# Encodeurs_Schematic.net
KiCad netlist of a schematic drawn in Altium Designer
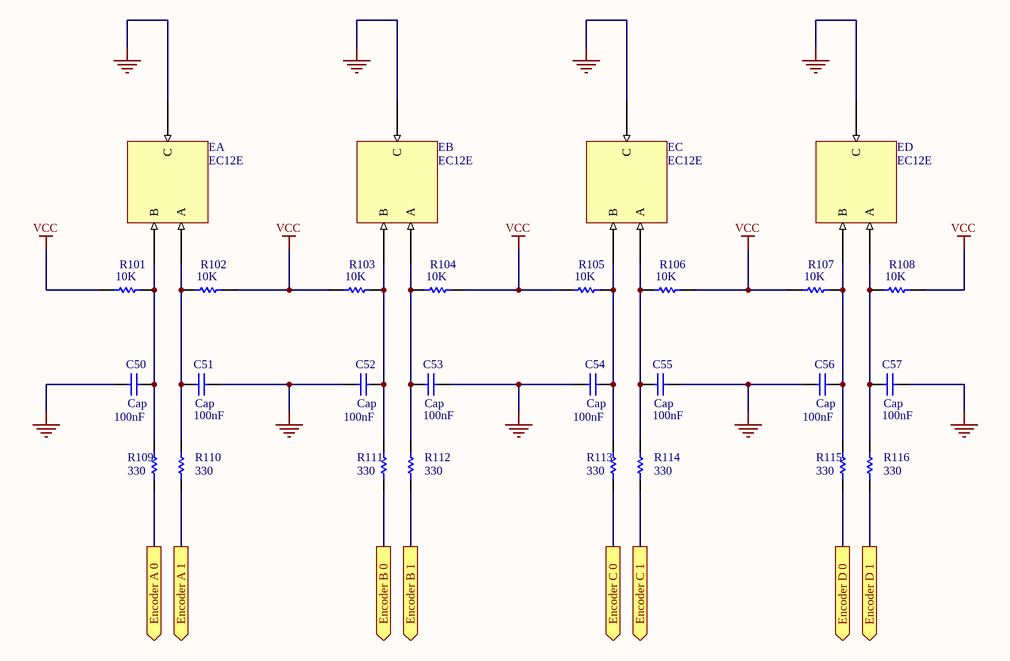
[diagram p0: Encodeurs.Schematic.SchDoc]

(export (version "E")
  (design (tool "Eeschema 10.0.6"))
  (components
    (comp (ref "C50")
      (value "Cap")
      (footprint "CAPC1608N")
      (description "Capacitor")
      (fields (field (name "ALTIUM_VALUE") "100nF") (field (name "PUBLISHER") "Altium Limited"))
      (libsource (lib "Miscellaneous Devices") (part "Cap"))
    )
    (comp (ref "C51")
      (value "Cap")
      (footprint "CAPC1608N")
      (description "Capacitor")
      (fields (field (name "ALTIUM_VALUE") "100nF") (field (name "PUBLISHER") "Altium Limited"))
      (libsource (lib "Miscellaneous Devices") (part "Cap"))
    )
    (comp (ref "C52")
      (value "Cap")
      (footprint "CAPC1608N")
      (description "Capacitor")
      (fields (field (name "ALTIUM_VALUE") "100nF") (field (name "PUBLISHER") "Altium Limited"))
      (libsource (lib "Miscellaneous Devices") (part "Cap"))
    )
    (comp (ref "C53")
      (value "Cap")
      (footprint "CAPC1608N")
      (description "Capacitor")
      (fields (field (name "ALTIUM_VALUE") "100nF") (field (name "PUBLISHER") "Altium Limited"))
      (libsource (lib "Miscellaneous Devices") (part "Cap"))
    )
    (comp (ref "C54")
      (value "Cap")
      (footprint "CAPC1608N")
      (description "Capacitor")
      (fields (field (name "ALTIUM_VALUE") "100nF") (field (name "PUBLISHER") "Altium Limited"))
      (libsource (lib "Miscellaneous Devices") (part "Cap"))
    )
    (comp (ref "C55")
      (value "Cap")
      (footprint "CAPC1608N")
      (description "Capacitor")
      (fields (field (name "ALTIUM_VALUE") "100nF") (field (name "PUBLISHER") "Altium Limited"))
      (libsource (lib "Miscellaneous Devices") (part "Cap"))
    )
    (comp (ref "C56")
      (value "Cap")
      (footprint "CAPC1608N")
      (description "Capacitor")
      (fields (field (name "ALTIUM_VALUE") "100nF") (field (name "PUBLISHER") "Altium Limited"))
      (libsource (lib "Miscellaneous Devices") (part "Cap"))
    )
    (comp (ref "C57")
      (value "Cap")
      (footprint "CAPC1608N")
      (description "Capacitor")
      (fields (field (name "ALTIUM_VALUE") "100nF") (field (name "PUBLISHER") "Altium Limited"))
      (libsource (lib "Miscellaneous Devices") (part "Cap"))
    )
    (comp (ref "EA")
      (value "EC12E")
      (footprint "EC12E")
      (libsource (lib "SynthyTwo.Components") (part "EC12E"))
    )
    (comp (ref "EB")
      (value "EC12E")
      (footprint "EC12E")
      (libsource (lib "SynthyTwo.Components") (part "EC12E"))
    )
    (comp (ref "EC")
      (value "EC12E")
      (footprint "EC12E")
      (libsource (lib "SynthyTwo.Components") (part "EC12E"))
    )
    (comp (ref "ED")
      (value "EC12E")
      (footprint "EC12E")
      (libsource (lib "SynthyTwo.Components") (part "EC12E"))
    )
    (comp (ref "R101")
      (value "10K")
      (footprint "CAPC1608N")
      (description "Resistor")
      (fields (field (name "PUBLISHER") "Altium Limited"))
      (libsource (lib "Miscellaneous Devices") (part "Res1"))
    )
    (comp (ref "R102")
      (value "10K")
      (footprint "CAPC1608N")
      (description "Resistor")
      (fields (field (name "PUBLISHER") "Altium Limited"))
      (libsource (lib "Miscellaneous Devices") (part "Res1"))
    )
    (comp (ref "R103")
      (value "10K")
      (footprint "CAPC1608N")
      (description "Resistor")
      (fields (field (name "PUBLISHER") "Altium Limited"))
      (libsource (lib "Miscellaneous Devices") (part "Res1"))
    )
    (comp (ref "R104")
      (value "10K")
      (footprint "CAPC1608N")
      (description "Resistor")
      (fields (field (name "PUBLISHER") "Altium Limited"))
      (libsource (lib "Miscellaneous Devices") (part "Res1"))
    )
    (comp (ref "R105")
      (value "10K")
      (footprint "CAPC1608N")
      (description "Resistor")
      (fields (field (name "PUBLISHER") "Altium Limited"))
      (libsource (lib "Miscellaneous Devices") (part "Res1"))
    )
    (comp (ref "R106")
      (value "10K")
      (footprint "CAPC1608N")
      (description "Resistor")
      (fields (field (name "PUBLISHER") "Altium Limited"))
      (libsource (lib "Miscellaneous Devices") (part "Res1"))
    )
    (comp (ref "R107")
      (value "10K")
      (footprint "CAPC1608N")
      (description "Resistor")
      (fields (field (name "PUBLISHER") "Altium Limited"))
      (libsource (lib "Miscellaneous Devices") (part "Res1"))
    )
    (comp (ref "R108")
      (value "10K")
      (footprint "CAPC1608N")
      (description "Resistor")
      (fields (field (name "PUBLISHER") "Altium Limited"))
      (libsource (lib "Miscellaneous Devices") (part "Res1"))
    )
    (comp (ref "R109")
      (value "330")
      (footprint "CAPC1608N")
      (description "Resistor")
      (fields (field (name "PUBLISHER") "Altium Limited"))
      (libsource (lib "Miscellaneous Devices") (part "Res1"))
    )
    (comp (ref "R110")
      (value "330")
      (footprint "CAPC1608N")
      (description "Resistor")
      (fields (field (name "PUBLISHER") "Altium Limited"))
      (libsource (lib "Miscellaneous Devices") (part "Res1"))
    )
    (comp (ref "R111")
      (value "330")
      (footprint "CAPC1608N")
      (description "Resistor")
      (fields (field (name "PUBLISHER") "Altium Limited"))
      (libsource (lib "Miscellaneous Devices") (part "Res1"))
    )
    (comp (ref "R112")
      (value "330")
      (footprint "CAPC1608N")
      (description "Resistor")
      (fields (field (name "PUBLISHER") "Altium Limited"))
      (libsource (lib "Miscellaneous Devices") (part "Res1"))
    )
    (comp (ref "R113")
      (value "330")
      (footprint "CAPC1608N")
      (description "Resistor")
      (fields (field (name "PUBLISHER") "Altium Limited"))
      (libsource (lib "Miscellaneous Devices") (part "Res1"))
    )
    (comp (ref "R114")
      (value "330")
      (footprint "CAPC1608N")
      (description "Resistor")
      (fields (field (name "PUBLISHER") "Altium Limited"))
      (libsource (lib "Miscellaneous Devices") (part "Res1"))
    )
    (comp (ref "R115")
      (value "330")
      (footprint "CAPC1608N")
      (description "Resistor")
      (fields (field (name "PUBLISHER") "Altium Limited"))
      (libsource (lib "Miscellaneous Devices") (part "Res1"))
    )
    (comp (ref "R116")
      (value "330")
      (footprint "CAPC1608N")
      (description "Resistor")
      (fields (field (name "PUBLISHER") "Altium Limited"))
      (libsource (lib "Miscellaneous Devices") (part "Res1"))
    )
  )
  (nets
    (net (code "1") (name "/Encoder A 0") (class "Default")
      (node (ref "R109") (pin "1") (pinfunction "1_1") (pintype "passive"))
    )
    (net (code "2") (name "/Encoder A 1") (class "Default")
      (node (ref "R110") (pin "1") (pinfunction "1_1") (pintype "passive"))
    )
    (net (code "3") (name "/Encoder B 0") (class "Default")
      (node (ref "R111") (pin "1") (pinfunction "1_1") (pintype "passive"))
    )
    (net (code "4") (name "/Encoder B 1") (class "Default")
      (node (ref "R112") (pin "1") (pinfunction "1_1") (pintype "passive"))
    )
    (net (code "5") (name "/Encoder C 0") (class "Default")
      (node (ref "R113") (pin "1") (pinfunction "1_1") (pintype "passive"))
    )
    (net (code "6") (name "/Encoder C 1") (class "Default")
      (node (ref "R114") (pin "1") (pinfunction "1_1") (pintype "passive"))
    )
    (net (code "7") (name "/Encoder D 0") (class "Default")
      (node (ref "R115") (pin "1") (pinfunction "1_1") (pintype "passive"))
    )
    (net (code "8") (name "/Encoder D 1") (class "Default")
      (node (ref "R116") (pin "1") (pinfunction "1_1") (pintype "passive"))
    )
    (net (code "9") (name "GND") (class "Default")
      (node (ref "C50") (pin "1") (pinfunction "1_1") (pintype "passive"))
      (node (ref "C51") (pin "1") (pinfunction "1_1") (pintype "passive"))
      (node (ref "C52") (pin "1") (pinfunction "1_1") (pintype "passive"))
      (node (ref "C53") (pin "1") (pinfunction "1_1") (pintype "passive"))
      (node (ref "C54") (pin "1") (pinfunction "1_1") (pintype "passive"))
      (node (ref "C55") (pin "1") (pinfunction "1_1") (pintype "passive"))
      (node (ref "C56") (pin "1") (pinfunction "1_1") (pintype "passive"))
      (node (ref "C57") (pin "1") (pinfunction "1_1") (pintype "passive"))
      (node (ref "EA") (pin "3") (pinfunction "C_3") (pintype "input"))
      (node (ref "EB") (pin "3") (pinfunction "C_3") (pintype "input"))
      (node (ref "EC") (pin "3") (pinfunction "C_3") (pintype "input"))
      (node (ref "ED") (pin "3") (pinfunction "C_3") (pintype "input"))
    )
    (net (code "10") (name "Net-(EA-A)") (class "Default")
      (node (ref "C51") (pin "2") (pinfunction "2_2") (pintype "passive"))
      (node (ref "EA") (pin "1") (pinfunction "A_1") (pintype "input"))
      (node (ref "R102") (pin "1") (pinfunction "1_1") (pintype "passive"))
      (node (ref "R110") (pin "2") (pinfunction "2_2") (pintype "passive"))
    )
    (net (code "11") (name "Net-(EA-B)") (class "Default")
      (node (ref "C50") (pin "2") (pinfunction "2_2") (pintype "passive"))
      (node (ref "EA") (pin "2") (pinfunction "B_2") (pintype "input"))
      (node (ref "R101") (pin "2") (pinfunction "2_2") (pintype "passive"))
      (node (ref "R109") (pin "2") (pinfunction "2_2") (pintype "passive"))
    )
    (net (code "12") (name "Net-(EB-A)") (class "Default")
      (node (ref "C53") (pin "2") (pinfunction "2_2") (pintype "passive"))
      (node (ref "EB") (pin "1") (pinfunction "A_1") (pintype "input"))
      (node (ref "R104") (pin "1") (pinfunction "1_1") (pintype "passive"))
      (node (ref "R112") (pin "2") (pinfunction "2_2") (pintype "passive"))
    )
    (net (code "13") (name "Net-(EB-B)") (class "Default")
      (node (ref "C52") (pin "2") (pinfunction "2_2") (pintype "passive"))
      (node (ref "EB") (pin "2") (pinfunction "B_2") (pintype "input"))
      (node (ref "R103") (pin "2") (pinfunction "2_2") (pintype "passive"))
      (node (ref "R111") (pin "2") (pinfunction "2_2") (pintype "passive"))
    )
    (net (code "14") (name "Net-(EC-A)") (class "Default")
      (node (ref "C55") (pin "2") (pinfunction "2_2") (pintype "passive"))
      (node (ref "EC") (pin "1") (pinfunction "A_1") (pintype "input"))
      (node (ref "R106") (pin "1") (pinfunction "1_1") (pintype "passive"))
      (node (ref "R114") (pin "2") (pinfunction "2_2") (pintype "passive"))
    )
    (net (code "15") (name "Net-(EC-B)") (class "Default")
      (node (ref "C54") (pin "2") (pinfunction "2_2") (pintype "passive"))
      (node (ref "EC") (pin "2") (pinfunction "B_2") (pintype "input"))
      (node (ref "R105") (pin "2") (pinfunction "2_2") (pintype "passive"))
      (node (ref "R113") (pin "2") (pinfunction "2_2") (pintype "passive"))
    )
    (net (code "16") (name "Net-(ED-A)") (class "Default")
      (node (ref "C57") (pin "2") (pinfunction "2_2") (pintype "passive"))
      (node (ref "ED") (pin "1") (pinfunction "A_1") (pintype "input"))
      (node (ref "R108") (pin "1") (pinfunction "1_1") (pintype "passive"))
      (node (ref "R116") (pin "2") (pinfunction "2_2") (pintype "passive"))
    )
    (net (code "17") (name "Net-(ED-B)") (class "Default")
      (node (ref "C56") (pin "2") (pinfunction "2_2") (pintype "passive"))
      (node (ref "ED") (pin "2") (pinfunction "B_2") (pintype "input"))
      (node (ref "R107") (pin "2") (pinfunction "2_2") (pintype "passive"))
      (node (ref "R115") (pin "2") (pinfunction "2_2") (pintype "passive"))
    )
    (net (code "18") (name "VCC") (class "Default")
      (node (ref "R101") (pin "1") (pinfunction "1_1") (pintype "passive"))
      (node (ref "R102") (pin "2") (pinfunction "2_2") (pintype "passive"))
      (node (ref "R103") (pin "1") (pinfunction "1_1") (pintype "passive"))
      (node (ref "R104") (pin "2") (pinfunction "2_2") (pintype "passive"))
      (node (ref "R105") (pin "1") (pinfunction "1_1") (pintype "passive"))
      (node (ref "R106") (pin "2") (pinfunction "2_2") (pintype "passive"))
      (node (ref "R107") (pin "1") (pinfunction "1_1") (pintype "passive"))
      (node (ref "R108") (pin "2") (pinfunction "2_2") (pintype "passive"))
    )
  )
)
